# v2.net
KiCad netlist of a schematic drawn in Altium Designer
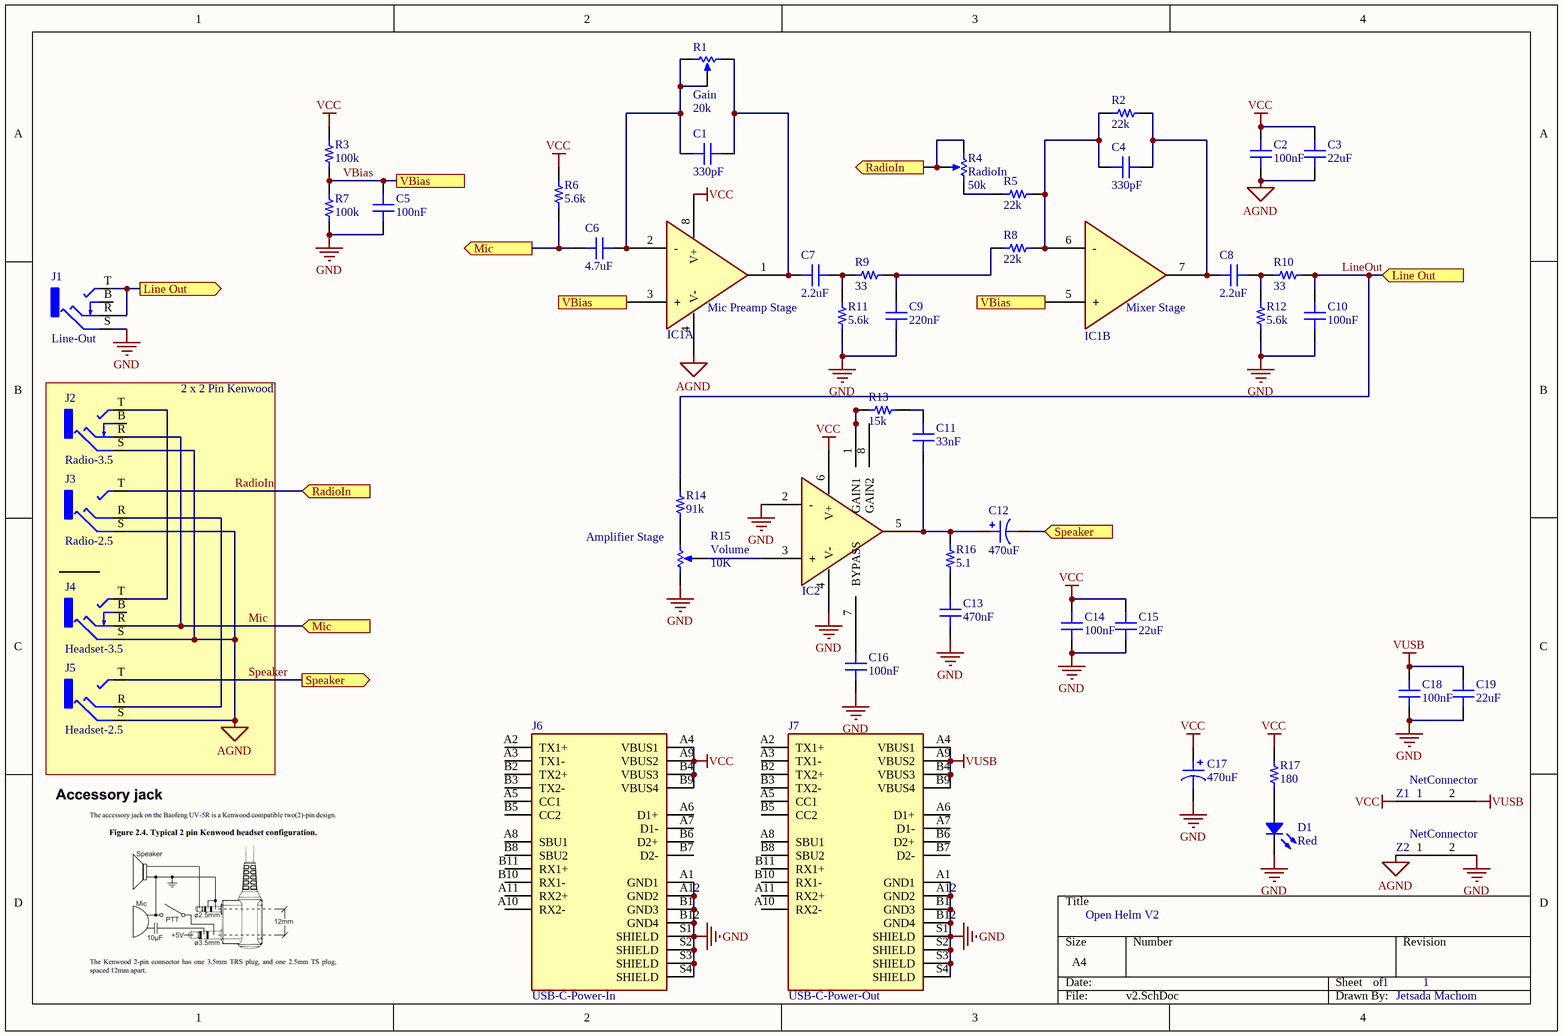
[diagram p0: v2.SchDoc]

(export (version "E")
  (design (tool "Eeschema 10.0.6"))
  (components
    (comp (ref "C1")
      (value "330pF")
      (footprint "CAP 0805_2012")
      (description "Multilayer Ceramic Capacitors MLCC - SMD/SMT 330pF 50V 0805 RoHS")
      (libsource (lib "Celestial Altium Library - altium_library") (part "Capacitor"))
    )
    (comp (ref "C2")
      (value "100nF")
      (footprint "CAP 0805_2012")
      (description "Multilayer Ceramic Capacitors MLCC - SMD/SMT 100nF 50V 0805 RoHS")
      (libsource (lib "Celestial Altium Library - altium_library") (part "Capacitor"))
    )
    (comp (ref "C3")
      (value "22uF")
      (footprint "CAP 0805_2012")
      (description "Multilayer Ceramic Capacitors MLCC - SMD/SMT 22uF 25V 0805 RoHS")
      (libsource (lib "Celestial Altium Library - altium_library") (part "Capacitor"))
    )
    (comp (ref "C4")
      (value "330pF")
      (footprint "CAP 0805_2012")
      (description "Multilayer Ceramic Capacitors MLCC - SMD/SMT 330pF 50V 0805 RoHS")
      (libsource (lib "Celestial Altium Library - altium_library") (part "Capacitor"))
    )
    (comp (ref "C5")
      (value "100nF")
      (footprint "CAP 0805_2012")
      (description "Multilayer Ceramic Capacitors MLCC - SMD/SMT 100nF 50V 0805 RoHS")
      (libsource (lib "Celestial Altium Library - altium_library") (part "Capacitor"))
    )
    (comp (ref "C6")
      (value "4.7uF")
      (footprint "CAP 0805_2012")
      (description "Multilayer Ceramic Capacitors MLCC - SMD/SMT 4.7uF 25V 0805 RoHS")
      (libsource (lib "Celestial Altium Library - altium_library") (part "Capacitor"))
    )
    (comp (ref "C7")
      (value "2.2uF")
      (footprint "CAP 0805_2012")
      (description "Multilayer Ceramic Capacitors MLCC - SMD/SMT 2.2uF 50V 0805 RoHS")
      (libsource (lib "Celestial Altium Library - altium_library") (part "Capacitor"))
    )
    (comp (ref "C8")
      (value "2.2uF")
      (footprint "CAP 0805_2012")
      (description "Multilayer Ceramic Capacitors MLCC - SMD/SMT 2.2uF 50V 0805 RoHS")
      (libsource (lib "Celestial Altium Library - altium_library") (part "Capacitor"))
    )
    (comp (ref "C9")
      (value "220nF")
      (footprint "CAP 0805_2012")
      (description "Multilayer Ceramic Capacitors MLCC - SMD/SMT 220nF 50V 0805 RoHS")
      (libsource (lib "Celestial Altium Library - altium_library") (part "Capacitor"))
    )
    (comp (ref "C10")
      (value "100nF")
      (footprint "CAP 0805_2012")
      (description "Multilayer Ceramic Capacitors MLCC - SMD/SMT 100nF 50V 0805 RoHS")
      (libsource (lib "Celestial Altium Library - altium_library") (part "Capacitor"))
    )
    (comp (ref "C11")
      (value "33nF")
      (footprint "CAP 0805_2012")
      (description "Multilayer Ceramic Capacitors MLCC - SMD/SMT 33nF 50V 0805 RoHS")
      (libsource (lib "Celestial Altium Library - altium_library") (part "Capacitor"))
    )
    (comp (ref "C12")
      (value "470uF")
      (footprint "EEEFT-D8")
      (description "SMD Aluminium Electrolytic Capacitor, Radial Can - SMD, 470 µF, 10 V, 0.16 ohm, FT Series")
      (libsource (lib "") (part "Polarised Capacitor_1"))
    )
    (comp (ref "C13")
      (value "470nF")
      (footprint "CAP 0805_2012")
      (description "Multilayer Ceramic Capacitors MLCC - SMD/SMT 470nF 50V 0805 RoHS")
      (libsource (lib "Celestial Altium Library - altium_library") (part "Capacitor"))
    )
    (comp (ref "C14")
      (value "100nF")
      (footprint "CAP 0805_2012")
      (description "Multilayer Ceramic Capacitors MLCC - SMD/SMT 100nF 50V 0805 RoHS")
      (libsource (lib "Celestial Altium Library - altium_library") (part "Capacitor"))
    )
    (comp (ref "C15")
      (value "22uF")
      (footprint "CAP 0805_2012")
      (description "Multilayer Ceramic Capacitors MLCC - SMD/SMT 22uF 25V 0805 RoHS")
      (libsource (lib "Celestial Altium Library - altium_library") (part "Capacitor"))
    )
    (comp (ref "C16")
      (value "100nF")
      (footprint "CAP 0805_2012")
      (description "Multilayer Ceramic Capacitors MLCC - SMD/SMT 100nF 50V 0805 RoHS")
      (libsource (lib "Celestial Altium Library - altium_library") (part "Capacitor"))
    )
    (comp (ref "C17")
      (value "470uF")
      (footprint "EEEFT-D8")
      (description "SMD Aluminium Electrolytic Capacitor, Radial Can - SMD, 470 µF, 10 V, 0.16 ohm, FT Series")
      (libsource (lib "Celestial Altium Library - altium_library") (part "Polarised Capacitor"))
    )
    (comp (ref "C18")
      (value "100nF")
      (footprint "CAP 0805_2012")
      (description "Multilayer Ceramic Capacitors MLCC - SMD/SMT 100nF 50V 0805 RoHS")
      (libsource (lib "Celestial Altium Library - altium_library") (part "Capacitor"))
    )
    (comp (ref "C19")
      (value "22uF")
      (footprint "CAP 0805_2012")
      (description "Multilayer Ceramic Capacitors MLCC - SMD/SMT 22uF 25V 0805 RoHS")
      (libsource (lib "Celestial Altium Library - altium_library") (part "Capacitor"))
    )
    (comp (ref "D1")
      (value "Red")
      (footprint "LED 0805_2012 RED")
      (description "LIGHT EMITTING DIODES (LED) RED 615~630NM 67~195MCD@20MA TOP VIEW 0805 ROHS")
      (libsource (lib "Celestial Altium Library - altium_library") (part "LED"))
    )
    (comp (ref "IC1") (value "LM4562") (footprint "LM4562") (libsource (lib "ZLib") (part "LM4562")))
    (comp (ref "IC2") (value "LM386") (footprint "LM386D") (libsource (lib "ZLib") (part "LM386")))
    (comp (ref "J1")
      (value "Line-Out")
      (footprint "KLBR4")
      (description "Phone Audio Connector, 3 Contacts, Socket, 3.5 mm, PCB Mount, Silver Plated Contacts, Metal Body")
      (libsource (lib "KLBR4") (part "KLBR4"))
    )
    (comp (ref "J2")
      (value "Radio-3.5")
      (footprint "KLBR4")
      (description "Phone Audio Connector, 3 Contacts, Socket, 3.5 mm, PCB Mount, Silver Plated Contacts, Metal Body")
      (libsource (lib "KLBR4") (part "KLBR4"))
    )
    (comp (ref "J3")
      (value "Radio-2.5")
      (footprint "LUMBERG150105")
      (description "Phone Audio Connector, 3 Contacts, Socket, 2.5 mm, PCB Mount, Silver Plated Contacts, Metal Body")
      (libsource (lib "ZLib") (part "LUMBERG150105"))
    )
    (comp (ref "J4")
      (value "Headset-3.5")
      (footprint "KLBR4")
      (description "Phone Audio Connector, 3 Contacts, Socket, 3.5 mm, PCB Mount, Silver Plated Contacts, Metal Body")
      (libsource (lib "KLBR4") (part "KLBR4"))
    )
    (comp (ref "J5")
      (value "Headset-2.5")
      (footprint "LUMBERG150105")
      (description "Phone Audio Connector, 3 Contacts, Socket, 2.5 mm, PCB Mount, Silver Plated Contacts, Metal Body")
      (libsource (lib "ZLib") (part "LUMBERG150105"))
    )
    (comp (ref "J6")
      (value "USB-C-Power-In")
      (footprint "MC001002")
      (description "USB Connector, USB Type C, USB 3.1, Receptacle, 24 Ways, Surface Mount, Through Hole Mount")
      (libsource (lib "ZLib") (part "USBC"))
    )
    (comp (ref "J7")
      (value "USB-C-Power-Out")
      (footprint "MC001002")
      (description "USB Connector, USB Type C, USB 3.1, Receptacle, 24 Ways, Surface Mount, Through Hole Mount")
      (libsource (lib "ZLib") (part "USBC"))
    )
    (comp (ref "R1")
      (value "Gain")
      (footprint "3224W")
      (description "20K ±10% ±100ppm/°C Variable Resistors")
      (fields (field (name "ALTIUM_VALUE") "20k"))
      (libsource (lib "ZLib") (part "RPot"))
    )
    (comp (ref "R2")
      (value "22k")
      (footprint "RES 0805_2012")
      (description "Chip Resistor - Surface Mount 22KOhms ±1% 1/8W 0805 RoHS")
      (libsource (lib "Celestial Altium Library - altium_library") (part "Resistor"))
    )
    (comp (ref "R3")
      (value "100k")
      (footprint "RES 0805_2012")
      (description "Chip Resistor - Surface Mount 100KOhms ±1% 1/8W 0805 RoHS")
      (libsource (lib "Celestial Altium Library - altium_library") (part "Resistor"))
    )
    (comp (ref "R4")
      (value "RadioIn")
      (footprint "3224W")
      (description "50K ±10% ±100ppm/°C Variable Resistors")
      (fields (field (name "ALTIUM_VALUE") "50k"))
      (libsource (lib "ZLib") (part "RPot"))
    )
    (comp (ref "R5")
      (value "22k")
      (footprint "RES 0805_2012")
      (description "Chip Resistor - Surface Mount 22KOhms ±1% 1/8W 0805 RoHS")
      (libsource (lib "Celestial Altium Library - altium_library") (part "Resistor"))
    )
    (comp (ref "R6")
      (value "5.6k")
      (footprint "RES 0805_2012")
      (description "Chip Resistor - Surface Mount 5.6KOhms ±1% 1/8W 0805 RoHS")
      (libsource (lib "Celestial Altium Library - altium_library") (part "Resistor"))
    )
    (comp (ref "R7")
      (value "100k")
      (footprint "RES 0805_2012")
      (description "Chip Resistor - Surface Mount 100KOhms ±1% 1/8W 0805 RoHS")
      (libsource (lib "Celestial Altium Library - altium_library") (part "Resistor"))
    )
    (comp (ref "R8")
      (value "22k")
      (footprint "RES 0805_2012")
      (description "Chip Resistor - Surface Mount 22KOhms ±1% 1/8W 0805 RoHS")
      (libsource (lib "Celestial Altium Library - altium_library") (part "Resistor"))
    )
    (comp (ref "R9")
      (value "33")
      (footprint "RES 0805_2012")
      (description "Chip Resistor - Surface Mount 33Ohms ±1% 1/8W 0805 RoHS")
      (libsource (lib "Celestial Altium Library - altium_library") (part "Resistor"))
    )
    (comp (ref "R10")
      (value "33")
      (footprint "RES 0805_2012")
      (description "Chip Resistor - Surface Mount 33Ohms ±1% 1/8W 0805 RoHS")
      (libsource (lib "Celestial Altium Library - altium_library") (part "Resistor"))
    )
    (comp (ref "R11")
      (value "5.6k")
      (footprint "RES 0805_2012")
      (description "Chip Resistor - Surface Mount 5.6KOhms ±1% 1/8W 0805 RoHS")
      (libsource (lib "Celestial Altium Library - altium_library") (part "Resistor"))
    )
    (comp (ref "R12")
      (value "5.6k")
      (footprint "RES 0805_2012")
      (description "Chip Resistor - Surface Mount 5.6KOhms ±1% 1/8W 0805 RoHS")
      (libsource (lib "Celestial Altium Library - altium_library") (part "Resistor"))
    )
    (comp (ref "R13")
      (value "15k")
      (footprint "RES 0805_2012")
      (description "Chip Resistor - Surface Mount 15KOhms ±1% 1/8W 0805 RoHS")
      (libsource (lib "Celestial Altium Library - altium_library") (part "Resistor"))
    )
    (comp (ref "R14")
      (value "91k")
      (footprint "RES 0805_2012")
      (description "Chip Resistor - Surface Mount 91KOhms ±1% 1/8W 0805 RoHS")
      (libsource (lib "Celestial Altium Library - altium_library") (part "Resistor"))
    )
    (comp (ref "R15")
      (value "Volume")
      (footprint "RK09")
      (description "Rotary Potentiometer, 10 kohm, 1 Turns, Logarithmic, 50 mW, ± 20%, RK09 Series")
      (fields (field (name "ALTIUM_VALUE") "10K"))
      (libsource (lib "ZLib") (part "RPot"))
    )
    (comp (ref "R16")
      (value "5.1")
      (footprint "RES 0805_2012")
      (description "Chip Resistor - Surface Mount 5.1Ohms ±1% 1/8W 0805 RoHS")
      (libsource (lib "Celestial Altium Library - altium_library") (part "Resistor"))
    )
    (comp (ref "R17")
      (value "180")
      (footprint "RES 0805_2012")
      (description "Chip Resistor - Surface Mount 180Ohms ±1% 1/8W 0805 RoHS")
      (libsource (lib "Celestial Altium Library - altium_library") (part "Resistor"))
    )
    (comp (ref "Z1")
      (value "NetConnector")
      (footprint "NetConnector")
      (libsource (lib "ZLib") (part "NetConnector"))
    )
    (comp (ref "Z2")
      (value "NetConnector")
      (footprint "NetConnector")
      (libsource (lib "ZLib") (part "NetConnector"))
    )
  )
  (nets
    (net (code "1") (name "/LineOut") (class "Default")
      (node (ref "C10") (pin "2") (pinfunction "2_2") (pintype "passive"))
      (node (ref "J1") (pin "R") (pinfunction "R_R") (pintype "passive"))
      (node (ref "J1") (pin "T") (pinfunction "T_T") (pintype "passive"))
      (node (ref "R10") (pin "1") (pinfunction "1_1") (pintype "passive"))
      (node (ref "R14") (pin "1") (pinfunction "1_1") (pintype "passive"))
    )
    (net (code "2") (name "/Mic") (class "Default")
      (node (ref "C6") (pin "1") (pinfunction "1_1") (pintype "passive"))
      (node (ref "J2") (pin "R") (pinfunction "R_R") (pintype "passive"))
      (node (ref "J4") (pin "R") (pinfunction "R_R") (pintype "passive"))
      (node (ref "R6") (pin "1") (pinfunction "1_1") (pintype "passive"))
    )
    (net (code "3") (name "/RadioIn") (class "Default")
      (node (ref "J3") (pin "T") (pinfunction "T_T") (pintype "passive"))
      (node (ref "R4") (pin "1") (pinfunction "TOP_1") (pintype "passive"))
      (node (ref "R4") (pin "2") (pinfunction "TAP_2") (pintype "passive"))
    )
    (net (code "4") (name "/Speaker") (class "Default")
      (node (ref "C12") (pin "2") (pinfunction "2_2") (pintype "passive"))
      (node (ref "J5") (pin "T") (pinfunction "T_T") (pintype "passive"))
    )
    (net (code "5") (name "/VBias") (class "Default")
      (node (ref "C5") (pin "2") (pinfunction "2_2") (pintype "passive"))
      (node (ref "IC1") (pin "3") (pinfunction "+_3") (pintype "passive"))
      (node (ref "IC1") (pin "5") (pinfunction "+_5") (pintype "passive"))
      (node (ref "R3") (pin "1") (pinfunction "1_1") (pintype "passive"))
      (node (ref "R7") (pin "2") (pinfunction "2_2") (pintype "passive"))
    )
    (net (code "6") (name "AGND") (class "Default")
      (node (ref "C2") (pin "1") (pinfunction "1_1") (pintype "passive"))
      (node (ref "C3") (pin "1") (pinfunction "1_1") (pintype "passive"))
      (node (ref "IC1") (pin "4") (pinfunction "V-_4") (pintype "power_in"))
      (node (ref "J2") (pin "S") (pinfunction "S_S") (pintype "passive"))
      (node (ref "J3") (pin "S") (pinfunction "S_S") (pintype "passive"))
      (node (ref "J4") (pin "S") (pinfunction "S_S") (pintype "passive"))
      (node (ref "J5") (pin "S") (pinfunction "S_S") (pintype "passive"))
      (node (ref "Z2") (pin "1") (pinfunction "1_1") (pintype "passive"))
    )
    (net (code "7") (name "GND") (class "Default")
      (node (ref "C10") (pin "1") (pinfunction "1_1") (pintype "passive"))
      (node (ref "C13") (pin "1") (pinfunction "1_1") (pintype "passive"))
      (node (ref "C14") (pin "1") (pinfunction "1_1") (pintype "passive"))
      (node (ref "C15") (pin "1") (pinfunction "1_1") (pintype "passive"))
      (node (ref "C16") (pin "1") (pinfunction "1_1") (pintype "passive"))
      (node (ref "C17") (pin "2") (pinfunction "2_2") (pintype "passive"))
      (node (ref "C18") (pin "1") (pinfunction "1_1") (pintype "passive"))
      (node (ref "C19") (pin "1") (pinfunction "1_1") (pintype "passive"))
      (node (ref "C5") (pin "1") (pinfunction "1_1") (pintype "passive"))
      (node (ref "C9") (pin "1") (pinfunction "1_1") (pintype "passive"))
      (node (ref "D1") (pin "2") (pinfunction "2_2") (pintype "passive"))
      (node (ref "IC2") (pin "2") (pinfunction "-_2") (pintype "passive"))
      (node (ref "IC2") (pin "4") (pinfunction "V-_4") (pintype "power_in"))
      (node (ref "J1") (pin "S") (pinfunction "S_S") (pintype "passive"))
      (node (ref "J6") (pin "A1") (pinfunction "GND1_A1") (pintype "passive"))
      (node (ref "J6") (pin "A12") (pinfunction "GND2_A12") (pintype "passive"))
      (node (ref "J6") (pin "B1") (pinfunction "GND3_B1") (pintype "passive"))
      (node (ref "J6") (pin "B12") (pinfunction "GND4_B12") (pintype "passive"))
      (node (ref "J6") (pin "S1") (pinfunction "SHIELD_S1") (pintype "passive"))
      (node (ref "J6") (pin "S2") (pinfunction "SHIELD_S2") (pintype "passive"))
      (node (ref "J6") (pin "S3") (pinfunction "SHIELD_S3") (pintype "passive"))
      (node (ref "J6") (pin "S4") (pinfunction "SHIELD_S4") (pintype "passive"))
      (node (ref "J7") (pin "A1") (pinfunction "GND1_A1") (pintype "passive"))
      (node (ref "J7") (pin "A12") (pinfunction "GND2_A12") (pintype "passive"))
      (node (ref "J7") (pin "B1") (pinfunction "GND3_B1") (pintype "passive"))
      (node (ref "J7") (pin "B12") (pinfunction "GND4_B12") (pintype "passive"))
      (node (ref "J7") (pin "S1") (pinfunction "SHIELD_S1") (pintype "passive"))
      (node (ref "J7") (pin "S2") (pinfunction "SHIELD_S2") (pintype "passive"))
      (node (ref "J7") (pin "S3") (pinfunction "SHIELD_S3") (pintype "passive"))
      (node (ref "J7") (pin "S4") (pinfunction "SHIELD_S4") (pintype "passive"))
      (node (ref "R11") (pin "1") (pinfunction "1_1") (pintype "passive"))
      (node (ref "R12") (pin "1") (pinfunction "1_1") (pintype "passive"))
      (node (ref "R15") (pin "1") (pinfunction "TOP_1") (pintype "passive"))
      (node (ref "R7") (pin "1") (pinfunction "1_1") (pintype "passive"))
      (node (ref "Z2") (pin "2") (pinfunction "2_2") (pintype "passive"))
    )
    (net (code "8") (name "Net-(C7-Pad2)") (class "Default")
      (node (ref "C7") (pin "2") (pinfunction "2_2") (pintype "passive"))
      (node (ref "R11") (pin "2") (pinfunction "2_2") (pintype "passive"))
      (node (ref "R9") (pin "2") (pinfunction "2_2") (pintype "passive"))
    )
    (net (code "9") (name "Net-(C8-Pad2)") (class "Default")
      (node (ref "C8") (pin "2") (pinfunction "2_2") (pintype "passive"))
      (node (ref "R10") (pin "2") (pinfunction "2_2") (pintype "passive"))
      (node (ref "R12") (pin "2") (pinfunction "2_2") (pintype "passive"))
    )
    (net (code "10") (name "Net-(C9-Pad2)") (class "Default")
      (node (ref "C9") (pin "2") (pinfunction "2_2") (pintype "passive"))
      (node (ref "R8") (pin "2") (pinfunction "2_2") (pintype "passive"))
      (node (ref "R9") (pin "1") (pinfunction "1_1") (pintype "passive"))
    )
    (net (code "11") (name "Net-(C11-Pad2)") (class "Default")
      (node (ref "C11") (pin "2") (pinfunction "2_2") (pintype "passive"))
      (node (ref "R13") (pin "1") (pinfunction "1_1") (pintype "passive"))
    )
    (net (code "12") (name "Net-(C13-Pad2)") (class "Default")
      (node (ref "C13") (pin "2") (pinfunction "2_2") (pintype "passive"))
      (node (ref "R16") (pin "2") (pinfunction "2_2") (pintype "passive"))
    )
    (net (code "13") (name "Net-(D1-Pad1)") (class "Default")
      (node (ref "D1") (pin "1") (pinfunction "1_1") (pintype "passive"))
      (node (ref "R17") (pin "1") (pinfunction "1_1") (pintype "passive"))
    )
    (net (code "14") (name "Net-(IC1A--)") (class "Default")
      (node (ref "C1") (pin "1") (pinfunction "1_1") (pintype "passive"))
      (node (ref "C6") (pin "2") (pinfunction "2_2") (pintype "passive"))
      (node (ref "IC1") (pin "2") (pinfunction "-_2") (pintype "passive"))
      (node (ref "R1") (pin "1") (pinfunction "TOP_1") (pintype "passive"))
      (node (ref "R1") (pin "2") (pinfunction "TAP_2") (pintype "passive"))
    )
    (net (code "15") (name "Net-(IC1A-OUT)") (class "Default")
      (node (ref "C1") (pin "2") (pinfunction "2_2") (pintype "passive"))
      (node (ref "C7") (pin "1") (pinfunction "1_1") (pintype "passive"))
      (node (ref "IC1") (pin "1") (pinfunction "OUT_1") (pintype "passive"))
      (node (ref "R1") (pin "3") (pinfunction "BOT_3") (pintype "passive"))
    )
    (net (code "16") (name "Net-(IC1B--)") (class "Default")
      (node (ref "C4") (pin "1") (pinfunction "1_1") (pintype "passive"))
      (node (ref "IC1") (pin "6") (pinfunction "-_6") (pintype "passive"))
      (node (ref "R2") (pin "2") (pinfunction "2_2") (pintype "passive"))
      (node (ref "R5") (pin "1") (pinfunction "1_1") (pintype "passive"))
      (node (ref "R8") (pin "1") (pinfunction "1_1") (pintype "passive"))
    )
    (net (code "17") (name "Net-(IC1B-OUT)") (class "Default")
      (node (ref "C4") (pin "2") (pinfunction "2_2") (pintype "passive"))
      (node (ref "C8") (pin "1") (pinfunction "1_1") (pintype "passive"))
      (node (ref "IC1") (pin "7") (pinfunction "OUT_7") (pintype "passive"))
      (node (ref "R2") (pin "1") (pinfunction "1_1") (pintype "passive"))
    )
    (net (code "18") (name "Net-(IC2-+)") (class "Default")
      (node (ref "IC2") (pin "3") (pinfunction "+_3") (pintype "passive"))
      (node (ref "R15") (pin "2") (pinfunction "TAP_2") (pintype "passive"))
    )
    (net (code "19") (name "Net-(IC2-BYPASS)") (class "Default")
      (node (ref "C16") (pin "2") (pinfunction "2_2") (pintype "passive"))
      (node (ref "IC2") (pin "7") (pinfunction "BYPASS_7") (pintype "passive"))
    )
    (net (code "20") (name "Net-(IC2-GAIN1)") (class "Default")
      (node (ref "IC2") (pin "1") (pinfunction "GAIN1_1") (pintype "passive"))
      (node (ref "R13") (pin "2") (pinfunction "2_2") (pintype "passive"))
    )
    (net (code "21") (name "Net-(IC2-OUT)") (class "Default")
      (node (ref "C11") (pin "1") (pinfunction "1_1") (pintype "passive"))
      (node (ref "C12") (pin "1") (pinfunction "1_1") (pintype "passive"))
      (node (ref "IC2") (pin "5") (pinfunction "OUT_5") (pintype "passive"))
      (node (ref "R16") (pin "1") (pinfunction "1_1") (pintype "passive"))
    )
    (net (code "22") (name "Net-(J2-PadT)") (class "Default")
      (node (ref "J2") (pin "T") (pinfunction "T_T") (pintype "passive"))
      (node (ref "J4") (pin "T") (pinfunction "T_T") (pintype "passive"))
    )
    (net (code "23") (name "Net-(J3-PadR)") (class "Default")
      (node (ref "J3") (pin "R") (pinfunction "R_R") (pintype "passive"))
      (node (ref "J5") (pin "R") (pinfunction "R_R") (pintype "passive"))
    )
    (net (code "24") (name "Net-(R4-BOT)") (class "Default")
      (node (ref "R4") (pin "3") (pinfunction "BOT_3") (pintype "passive"))
      (node (ref "R5") (pin "2") (pinfunction "2_2") (pintype "passive"))
    )
    (net (code "25") (name "Net-(R15-BOT)") (class "Default")
      (node (ref "R14") (pin "2") (pinfunction "2_2") (pintype "passive"))
      (node (ref "R15") (pin "3") (pinfunction "BOT_3") (pintype "passive"))
    )
    (net (code "26") (name "VCC") (class "Default")
      (node (ref "C14") (pin "2") (pinfunction "2_2") (pintype "passive"))
      (node (ref "C15") (pin "2") (pinfunction "2_2") (pintype "passive"))
      (node (ref "C17") (pin "1") (pinfunction "1_1") (pintype "passive"))
      (node (ref "C2") (pin "2") (pinfunction "2_2") (pintype "passive"))
      (node (ref "C3") (pin "2") (pinfunction "2_2") (pintype "passive"))
      (node (ref "IC1") (pin "8") (pinfunction "V+_8") (pintype "power_in"))
      (node (ref "IC2") (pin "6") (pinfunction "V+_6") (pintype "power_in"))
      (node (ref "J6") (pin "A4") (pinfunction "VBUS1_A4") (pintype "passive"))
      (node (ref "J6") (pin "A9") (pinfunction "VBUS2_A9") (pintype "passive"))
      (node (ref "J6") (pin "B4") (pinfunction "VBUS3_B4") (pintype "passive"))
      (node (ref "J6") (pin "B9") (pinfunction "VBUS4_B9") (pintype "passive"))
      (node (ref "R17") (pin "2") (pinfunction "2_2") (pintype "passive"))
      (node (ref "R3") (pin "2") (pinfunction "2_2") (pintype "passive"))
      (node (ref "R6") (pin "2") (pinfunction "2_2") (pintype "passive"))
      (node (ref "Z1") (pin "1") (pinfunction "1_1") (pintype "passive"))
    )
    (net (code "27") (name "VUSB") (class "Default")
      (node (ref "C18") (pin "2") (pinfunction "2_2") (pintype "passive"))
      (node (ref "C19") (pin "2") (pinfunction "2_2") (pintype "passive"))
      (node (ref "J7") (pin "A4") (pinfunction "VBUS1_A4") (pintype "passive"))
      (node (ref "J7") (pin "A9") (pinfunction "VBUS2_A9") (pintype "passive"))
      (node (ref "J7") (pin "B4") (pinfunction "VBUS3_B4") (pintype "passive"))
      (node (ref "J7") (pin "B9") (pinfunction "VBUS4_B9") (pintype "passive"))
      (node (ref "Z1") (pin "2") (pinfunction "2_2") (pintype "passive"))
    )
    (net (code "28") (name "unconnected-(IC2-GAIN2-Pad8)") (class "Default")
      (node (ref "IC2") (pin "8") (pinfunction "GAIN2_8") (pintype "passive"))
    )
    (net (code "29") (name "unconnected-(J1-PadB)") (class "Default")
      (node (ref "J1") (pin "B") (pinfunction "B_B") (pintype "passive"))
    )
    (net (code "30") (name "unconnected-(J2-PadB)") (class "Default")
      (node (ref "J2") (pin "B") (pinfunction "B_B") (pintype "passive"))
    )
    (net (code "31") (name "unconnected-(J4-PadB)") (class "Default")
      (node (ref "J4") (pin "B") (pinfunction "B_B") (pintype "passive"))
    )
    (net (code "32") (name "unconnected-(J6-CC1-PadA5)") (class "Default")
      (node (ref "J6") (pin "A5") (pinfunction "CC1_A5") (pintype "passive"))
    )
    (net (code "33") (name "unconnected-(J6-CC2-PadB5)") (class "Default")
      (node (ref "J6") (pin "B5") (pinfunction "CC2_B5") (pintype "passive"))
    )
    (net (code "34") (name "unconnected-(J6-D1+-PadA6)") (class "Default")
      (node (ref "J6") (pin "A6") (pinfunction "D1+_A6") (pintype "passive"))
    )
    (net (code "35") (name "unconnected-(J6-D1--PadA7)") (class "Default")
      (node (ref "J6") (pin "A7") (pinfunction "D1-_A7") (pintype "passive"))
    )
    (net (code "36") (name "unconnected-(J6-D2+-PadB6)") (class "Default")
      (node (ref "J6") (pin "B6") (pinfunction "D2+_B6") (pintype "passive"))
    )
    (net (code "37") (name "unconnected-(J6-D2--PadB7)") (class "Default")
      (node (ref "J6") (pin "B7") (pinfunction "D2-_B7") (pintype "passive"))
    )
    (net (code "38") (name "unconnected-(J6-RX1+-PadB11)") (class "Default")
      (node (ref "J6") (pin "B11") (pinfunction "RX1+_B11") (pintype "passive"))
    )
    (net (code "39") (name "unconnected-(J6-RX1--PadB10)") (class "Default")
      (node (ref "J6") (pin "B10") (pinfunction "RX1-_B10") (pintype "passive"))
    )
    (net (code "40") (name "unconnected-(J6-RX2+-PadA11)") (class "Default")
      (node (ref "J6") (pin "A11") (pinfunction "RX2+_A11") (pintype "passive"))
    )
    (net (code "41") (name "unconnected-(J6-RX2--PadA10)") (class "Default")
      (node (ref "J6") (pin "A10") (pinfunction "RX2-_A10") (pintype "passive"))
    )
    (net (code "42") (name "unconnected-(J6-SBU1-PadA8)") (class "Default")
      (node (ref "J6") (pin "A8") (pinfunction "SBU1_A8") (pintype "passive"))
    )
    (net (code "43") (name "unconnected-(J6-SBU2-PadB8)") (class "Default")
      (node (ref "J6") (pin "B8") (pinfunction "SBU2_B8") (pintype "passive"))
    )
    (net (code "44") (name "unconnected-(J6-TX1+-PadA2)") (class "Default")
      (node (ref "J6") (pin "A2") (pinfunction "TX1+_A2") (pintype "passive"))
    )
    (net (code "45") (name "unconnected-(J6-TX1--PadA3)") (class "Default")
      (node (ref "J6") (pin "A3") (pinfunction "TX1-_A3") (pintype "passive"))
    )
    (net (code "46") (name "unconnected-(J6-TX2+-PadB2)") (class "Default")
      (node (ref "J6") (pin "B2") (pinfunction "TX2+_B2") (pintype "passive"))
    )
    (net (code "47") (name "unconnected-(J6-TX2--PadB3)") (class "Default")
      (node (ref "J6") (pin "B3") (pinfunction "TX2-_B3") (pintype "passive"))
    )
    (net (code "48") (name "unconnected-(J7-CC1-PadA5)") (class "Default")
      (node (ref "J7") (pin "A5") (pinfunction "CC1_A5") (pintype "passive"))
    )
    (net (code "49") (name "unconnected-(J7-CC2-PadB5)") (class "Default")
      (node (ref "J7") (pin "B5") (pinfunction "CC2_B5") (pintype "passive"))
    )
    (net (code "50") (name "unconnected-(J7-D1+-PadA6)") (class "Default")
      (node (ref "J7") (pin "A6") (pinfunction "D1+_A6") (pintype "passive"))
    )
    (net (code "51") (name "unconnected-(J7-D1--PadA7)") (class "Default")
      (node (ref "J7") (pin "A7") (pinfunction "D1-_A7") (pintype "passive"))
    )
    (net (code "52") (name "unconnected-(J7-D2+-PadB6)") (class "Default")
      (node (ref "J7") (pin "B6") (pinfunction "D2+_B6") (pintype "passive"))
    )
    (net (code "53") (name "unconnected-(J7-D2--PadB7)") (class "Default")
      (node (ref "J7") (pin "B7") (pinfunction "D2-_B7") (pintype "passive"))
    )
    (net (code "54") (name "unconnected-(J7-RX1+-PadB11)") (class "Default")
      (node (ref "J7") (pin "B11") (pinfunction "RX1+_B11") (pintype "passive"))
    )
    (net (code "55") (name "unconnected-(J7-RX1--PadB10)") (class "Default")
      (node (ref "J7") (pin "B10") (pinfunction "RX1-_B10") (pintype "passive"))
    )
    (net (code "56") (name "unconnected-(J7-RX2+-PadA11)") (class "Default")
      (node (ref "J7") (pin "A11") (pinfunction "RX2+_A11") (pintype "passive"))
    )
    (net (code "57") (name "unconnected-(J7-RX2--PadA10)") (class "Default")
      (node (ref "J7") (pin "A10") (pinfunction "RX2-_A10") (pintype "passive"))
    )
    (net (code "58") (name "unconnected-(J7-SBU1-PadA8)") (class "Default")
      (node (ref "J7") (pin "A8") (pinfunction "SBU1_A8") (pintype "passive"))
    )
    (net (code "59") (name "unconnected-(J7-SBU2-PadB8)") (class "Default")
      (node (ref "J7") (pin "B8") (pinfunction "SBU2_B8") (pintype "passive"))
    )
    (net (code "60") (name "unconnected-(J7-TX1+-PadA2)") (class "Default")
      (node (ref "J7") (pin "A2") (pinfunction "TX1+_A2") (pintype "passive"))
    )
    (net (code "61") (name "unconnected-(J7-TX1--PadA3)") (class "Default")
      (node (ref "J7") (pin "A3") (pinfunction "TX1-_A3") (pintype "passive"))
    )
    (net (code "62") (name "unconnected-(J7-TX2+-PadB2)") (class "Default")
      (node (ref "J7") (pin "B2") (pinfunction "TX2+_B2") (pintype "passive"))
    )
    (net (code "63") (name "unconnected-(J7-TX2--PadB3)") (class "Default")
      (node (ref "J7") (pin "B3") (pinfunction "TX2-_B3") (pintype "passive"))
    )
  )
)
